# Schematic4.net
KiCad netlist of a schematic drawn in Altium Designer
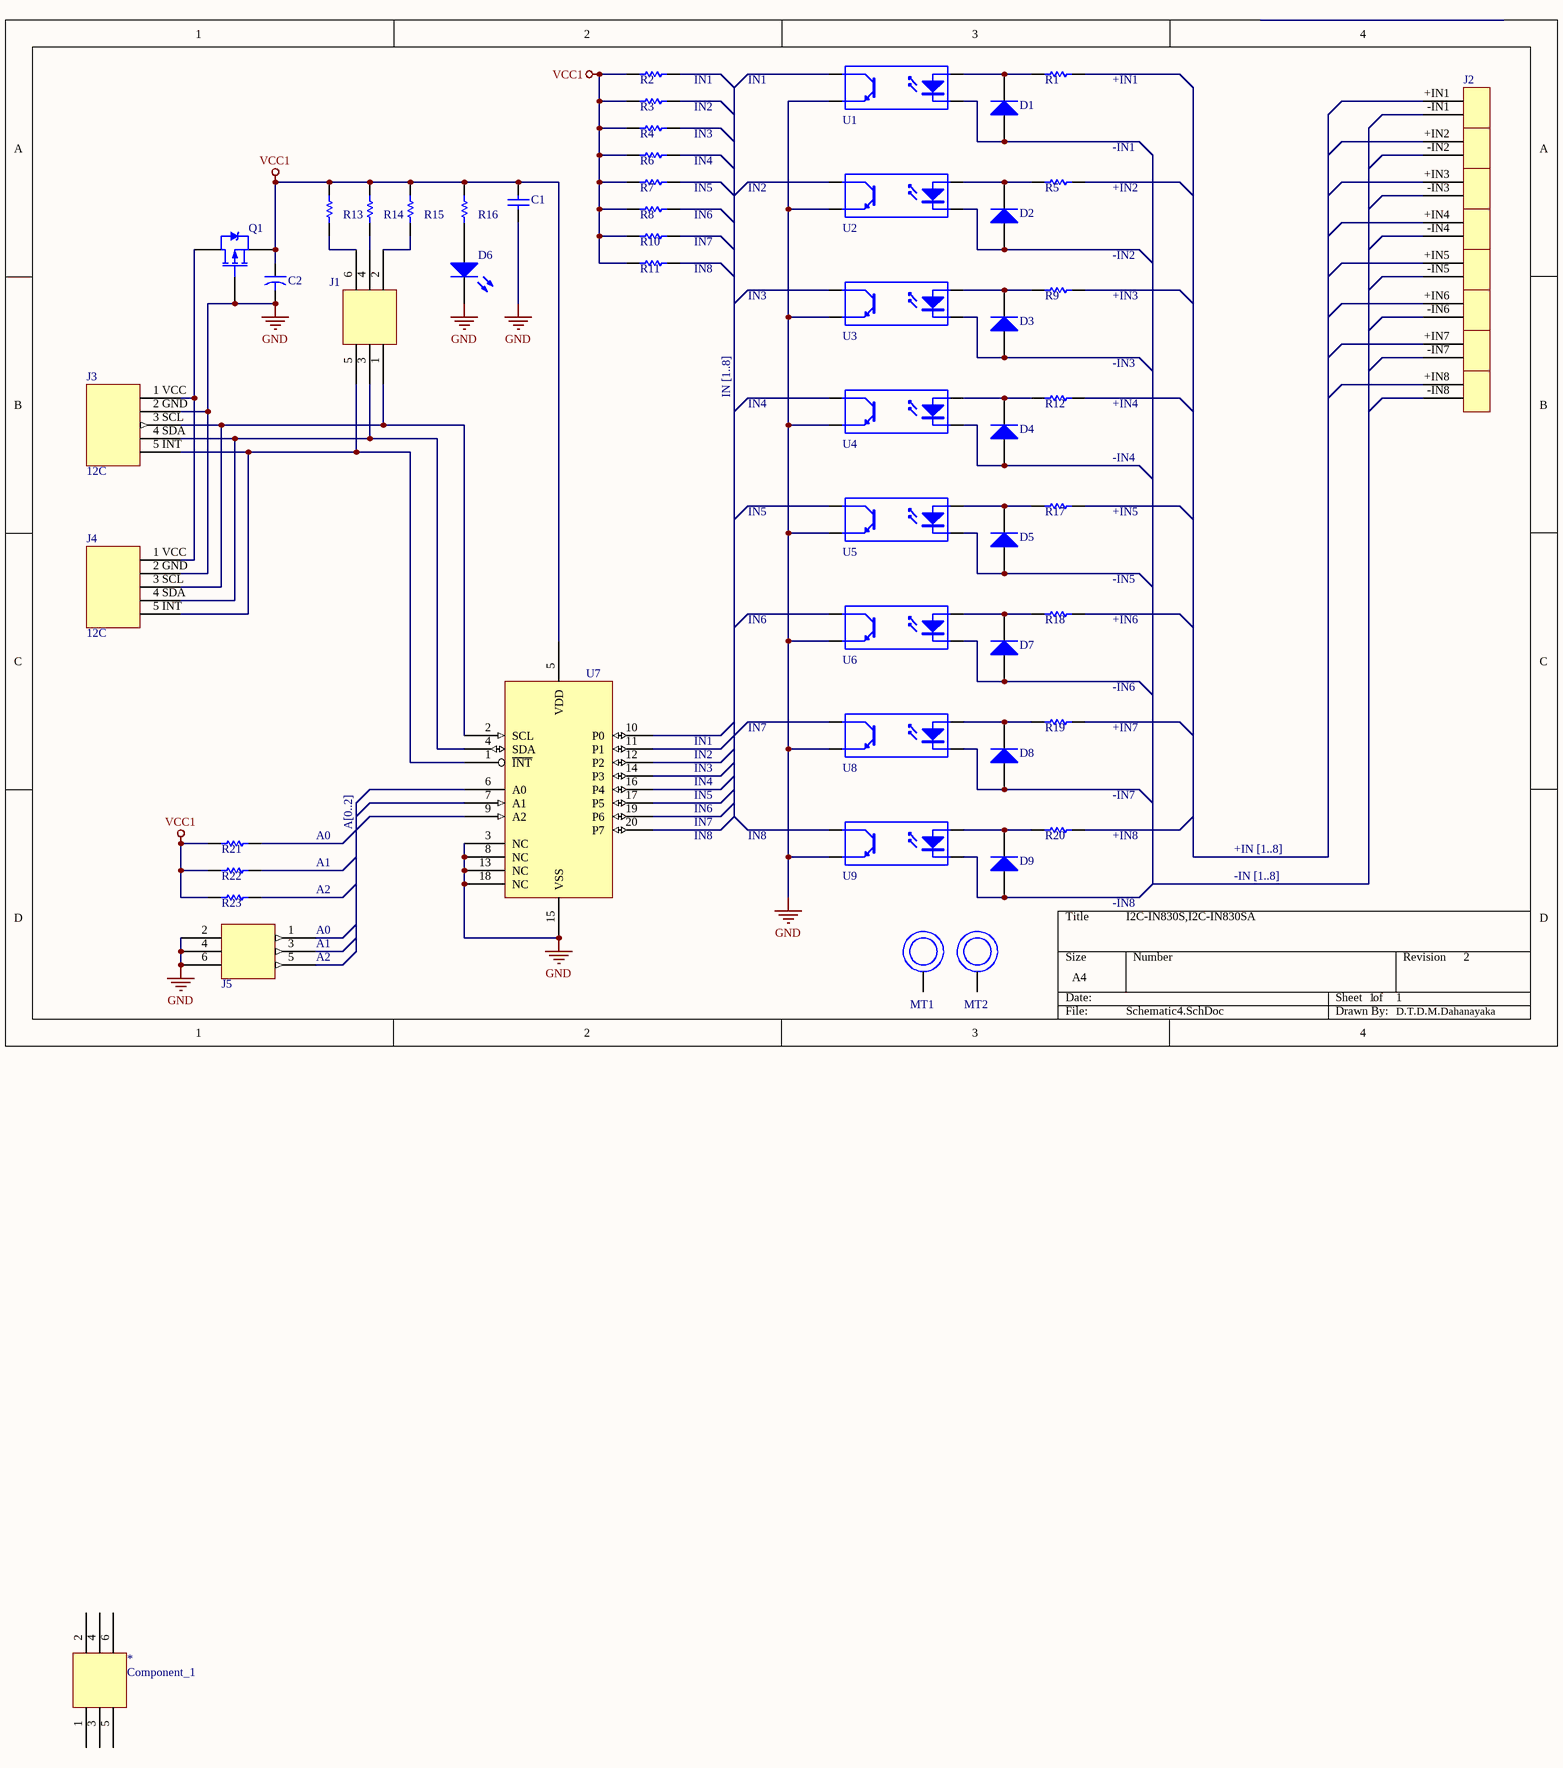
[diagram p0: Schematic4.SchDoc]

(export (version "E")
  (design (tool "Eeschema 10.0.6"))
  (components
    (comp (ref "*") (value "Component_1") (libsource (lib "J2") (part "Component_1")))
    (comp (ref "C1")
      (value "Cap")
      (footprint "RAD-0.3")
      (description "Capacitor")
      (fields (field (name "PUBLISHER") "Altium Limited"))
      (libsource (lib "Miscellaneous Devices") (part "Cap"))
    )
    (comp (ref "C2")
      (value "Cap2")
      (footprint "CAPR5-4X5")
      (description "Capacitor")
      (fields (field (name "PUBLISHER") "Altium Limited"))
      (libsource (lib "Miscellaneous Devices") (part "Cap2"))
    )
    (comp (ref "D1")
      (value "~")
      (footprint "SOT-23_N")
      (description "Silicon Low Leakage Diode")
      (fields (field (name "PUBLISHER") "Altium Limited"))
      (libsource (lib "Miscellaneous Devices") (part "Diode BAS116"))
    )
    (comp (ref "D2")
      (value "~")
      (footprint "SOT-23_N")
      (description "Silicon Low Leakage Diode")
      (fields (field (name "PUBLISHER") "Altium Limited"))
      (libsource (lib "Miscellaneous Devices") (part "Diode BAS116"))
    )
    (comp (ref "D3")
      (value "~")
      (footprint "SOT-23_N")
      (description "Silicon Low Leakage Diode")
      (fields (field (name "PUBLISHER") "Altium Limited"))
      (libsource (lib "Miscellaneous Devices") (part "Diode BAS116"))
    )
    (comp (ref "D4")
      (value "~")
      (footprint "SOT-23_N")
      (description "Silicon Low Leakage Diode")
      (fields (field (name "PUBLISHER") "Altium Limited"))
      (libsource (lib "Miscellaneous Devices") (part "Diode BAS116"))
    )
    (comp (ref "D5")
      (value "~")
      (footprint "SOT-23_N")
      (description "Silicon Low Leakage Diode")
      (fields (field (name "PUBLISHER") "Altium Limited"))
      (libsource (lib "Miscellaneous Devices") (part "Diode BAS116"))
    )
    (comp (ref "D6")
      (value "~")
      (footprint "LED-0")
      (description "Typical INFRARED GaAs LED")
      (fields (field (name "PUBLISHER") "Altium Limited"))
      (libsource (lib "Miscellaneous Devices") (part "LED0"))
    )
    (comp (ref "D7")
      (value "~")
      (footprint "SOT-23_N")
      (description "Silicon Low Leakage Diode")
      (fields (field (name "PUBLISHER") "Altium Limited"))
      (libsource (lib "Miscellaneous Devices") (part "Diode BAS116"))
    )
    (comp (ref "D8")
      (value "~")
      (footprint "SOT-23_N")
      (description "Silicon Low Leakage Diode")
      (fields (field (name "PUBLISHER") "Altium Limited"))
      (libsource (lib "Miscellaneous Devices") (part "Diode BAS116"))
    )
    (comp (ref "D9")
      (value "~")
      (footprint "SOT-23_N")
      (description "Silicon Low Leakage Diode")
      (fields (field (name "PUBLISHER") "Altium Limited"))
      (libsource (lib "Miscellaneous Devices") (part "Diode BAS116"))
    )
    (comp (ref "J1") (value "~") (libsource (lib "") (part "Component_1_1")))
    (comp (ref "J2") (value "~") (libsource (lib "J6") (part "Component_1")))
    (comp (ref "J3") (value "12C") (libsource (lib "J1") (part "Component_1")))
    (comp (ref "J4") (value "12C") (libsource (lib "J1") (part "Component_1")))
    (comp (ref "J5") (value "~") (libsource (lib "") (part "Component_1_2")))
    (comp (ref "MT1") (value "~") (libsource (lib "mt") (part "Component_1")))
    (comp (ref "MT2") (value "~") (libsource (lib "mt") (part "Component_1")))
    (comp (ref "Q1")
      (value "PMOS-2")
      (footprint "TO-220AB")
      (description "P-Channel Power MOSFET")
      (fields (field (name "PUBLISHER") "Altium Limited"))
      (libsource (lib "Miscellaneous Devices") (part "PMOS-2"))
    )
    (comp (ref "R1")
      (value "Res1")
      (footprint "AXIAL-0.3")
      (description "Resistor")
      (fields (field (name "PUBLISHER") "Altium Limited"))
      (libsource (lib "Miscellaneous Devices") (part "Res1"))
    )
    (comp (ref "R2")
      (value "Res1")
      (footprint "AXIAL-0.3")
      (description "Resistor")
      (fields (field (name "PUBLISHER") "Altium Limited"))
      (libsource (lib "Miscellaneous Devices") (part "Res1"))
    )
    (comp (ref "R3")
      (value "Res1")
      (footprint "AXIAL-0.3")
      (description "Resistor")
      (fields (field (name "PUBLISHER") "Altium Limited"))
      (libsource (lib "Miscellaneous Devices") (part "Res1"))
    )
    (comp (ref "R4")
      (value "Res1")
      (footprint "AXIAL-0.3")
      (description "Resistor")
      (fields (field (name "PUBLISHER") "Altium Limited"))
      (libsource (lib "Miscellaneous Devices") (part "Res1"))
    )
    (comp (ref "R5")
      (value "Res1")
      (footprint "AXIAL-0.3")
      (description "Resistor")
      (fields (field (name "PUBLISHER") "Altium Limited"))
      (libsource (lib "Miscellaneous Devices") (part "Res1"))
    )
    (comp (ref "R6")
      (value "Res1")
      (footprint "AXIAL-0.3")
      (description "Resistor")
      (fields (field (name "PUBLISHER") "Altium Limited"))
      (libsource (lib "Miscellaneous Devices") (part "Res1"))
    )
    (comp (ref "R7")
      (value "Res1")
      (footprint "AXIAL-0.3")
      (description "Resistor")
      (fields (field (name "PUBLISHER") "Altium Limited"))
      (libsource (lib "Miscellaneous Devices") (part "Res1"))
    )
    (comp (ref "R8")
      (value "Res1")
      (footprint "AXIAL-0.3")
      (description "Resistor")
      (fields (field (name "PUBLISHER") "Altium Limited"))
      (libsource (lib "Miscellaneous Devices") (part "Res1"))
    )
    (comp (ref "R9")
      (value "Res1")
      (footprint "AXIAL-0.3")
      (description "Resistor")
      (fields (field (name "PUBLISHER") "Altium Limited"))
      (libsource (lib "Miscellaneous Devices") (part "Res1"))
    )
    (comp (ref "R10")
      (value "Res1")
      (footprint "AXIAL-0.3")
      (description "Resistor")
      (fields (field (name "PUBLISHER") "Altium Limited"))
      (libsource (lib "Miscellaneous Devices") (part "Res1"))
    )
    (comp (ref "R11")
      (value "Res1")
      (footprint "AXIAL-0.3")
      (description "Resistor")
      (fields (field (name "PUBLISHER") "Altium Limited"))
      (libsource (lib "Miscellaneous Devices") (part "Res1"))
    )
    (comp (ref "R12")
      (value "Res1")
      (footprint "AXIAL-0.3")
      (description "Resistor")
      (fields (field (name "PUBLISHER") "Altium Limited"))
      (libsource (lib "Miscellaneous Devices") (part "Res1"))
    )
    (comp (ref "R13")
      (value "Res1")
      (footprint "AXIAL-0.3")
      (description "Resistor")
      (fields (field (name "PUBLISHER") "Altium Limited"))
      (libsource (lib "Miscellaneous Devices") (part "Res1"))
    )
    (comp (ref "R14")
      (value "Res1")
      (footprint "AXIAL-0.3")
      (description "Resistor")
      (fields (field (name "PUBLISHER") "Altium Limited"))
      (libsource (lib "Miscellaneous Devices") (part "Res1"))
    )
    (comp (ref "R15")
      (value "Res1")
      (footprint "AXIAL-0.3")
      (description "Resistor")
      (fields (field (name "PUBLISHER") "Altium Limited"))
      (libsource (lib "Miscellaneous Devices") (part "Res1"))
    )
    (comp (ref "R16")
      (value "Res1")
      (footprint "AXIAL-0.3")
      (description "Resistor")
      (fields (field (name "PUBLISHER") "Altium Limited"))
      (libsource (lib "Miscellaneous Devices") (part "Res1"))
    )
    (comp (ref "R17")
      (value "Res1")
      (footprint "AXIAL-0.3")
      (description "Resistor")
      (fields (field (name "PUBLISHER") "Altium Limited"))
      (libsource (lib "Miscellaneous Devices") (part "Res1"))
    )
    (comp (ref "R18")
      (value "Res1")
      (footprint "AXIAL-0.3")
      (description "Resistor")
      (fields (field (name "PUBLISHER") "Altium Limited"))
      (libsource (lib "Miscellaneous Devices") (part "Res1"))
    )
    (comp (ref "R19")
      (value "Res1")
      (footprint "AXIAL-0.3")
      (description "Resistor")
      (fields (field (name "PUBLISHER") "Altium Limited"))
      (libsource (lib "Miscellaneous Devices") (part "Res1"))
    )
    (comp (ref "R20")
      (value "Res1")
      (footprint "AXIAL-0.3")
      (description "Resistor")
      (fields (field (name "PUBLISHER") "Altium Limited"))
      (libsource (lib "Miscellaneous Devices") (part "Res1"))
    )
    (comp (ref "R21")
      (value "Res1")
      (footprint "AXIAL-0.3")
      (description "Resistor")
      (fields (field (name "PUBLISHER") "Altium Limited"))
      (libsource (lib "Miscellaneous Devices") (part "Res1"))
    )
    (comp (ref "R22")
      (value "Res1")
      (footprint "AXIAL-0.3")
      (description "Resistor")
      (fields (field (name "PUBLISHER") "Altium Limited"))
      (libsource (lib "Miscellaneous Devices") (part "Res1"))
    )
    (comp (ref "R23")
      (value "Res1")
      (footprint "AXIAL-0.3")
      (description "Resistor")
      (fields (field (name "PUBLISHER") "Altium Limited"))
      (libsource (lib "Miscellaneous Devices") (part "Res1"))
    )
    (comp (ref "U1")
      (value "~")
      (footprint "DIP-4")
      (description "4-Pin Phototransistor Optocoupler")
      (fields (field (name "PUBLISHER") "Altium Limited"))
      (libsource (lib "Miscellaneous Devices") (part "Optoisolator1"))
    )
    (comp (ref "U2")
      (value "~")
      (footprint "DIP-4")
      (description "4-Pin Phototransistor Optocoupler")
      (fields (field (name "PUBLISHER") "Altium Limited"))
      (libsource (lib "Miscellaneous Devices") (part "Optoisolator1"))
    )
    (comp (ref "U3")
      (value "~")
      (footprint "DIP-4")
      (description "4-Pin Phototransistor Optocoupler")
      (fields (field (name "PUBLISHER") "Altium Limited"))
      (libsource (lib "Miscellaneous Devices") (part "Optoisolator1"))
    )
    (comp (ref "U4")
      (value "~")
      (footprint "DIP-4")
      (description "4-Pin Phototransistor Optocoupler")
      (fields (field (name "PUBLISHER") "Altium Limited"))
      (libsource (lib "Miscellaneous Devices") (part "Optoisolator1"))
    )
    (comp (ref "U5")
      (value "~")
      (footprint "DIP-4")
      (description "4-Pin Phototransistor Optocoupler")
      (fields (field (name "PUBLISHER") "Altium Limited"))
      (libsource (lib "Miscellaneous Devices") (part "Optoisolator1"))
    )
    (comp (ref "U6")
      (value "~")
      (footprint "DIP-4")
      (description "4-Pin Phototransistor Optocoupler")
      (fields (field (name "PUBLISHER") "Altium Limited"))
      (libsource (lib "Miscellaneous Devices") (part "Optoisolator1"))
    )
    (comp (ref "U7") (value "~") (libsource (lib "U1") (part "Component_1")))
    (comp (ref "U8")
      (value "~")
      (footprint "DIP-4")
      (description "4-Pin Phototransistor Optocoupler")
      (fields (field (name "PUBLISHER") "Altium Limited"))
      (libsource (lib "Miscellaneous Devices") (part "Optoisolator1"))
    )
    (comp (ref "U9")
      (value "~")
      (footprint "DIP-4")
      (description "4-Pin Phototransistor Optocoupler")
      (fields (field (name "PUBLISHER") "Altium Limited"))
      (libsource (lib "Miscellaneous Devices") (part "Optoisolator1"))
    )
  )
  (nets
    (net (code "1") (name "GND") (class "Default")
      (node (ref "C1") (pin "1") (pinfunction "1_1") (pintype "passive"))
      (node (ref "C2") (pin "2") (pinfunction "2_2") (pintype "passive"))
      (node (ref "D6") (pin "2") (pinfunction "K_2") (pintype "passive"))
      (node (ref "J3") (pin "2_GND") (pintype "passive"))
      (node (ref "J4") (pin "2_GND") (pintype "passive"))
      (node (ref "J5") (pin "2") (pintype "passive"))
      (node (ref "J5") (pin "4") (pintype "passive"))
      (node (ref "J5") (pin "6") (pintype "passive"))
      (node (ref "Q1") (pin "1") (pinfunction "G_1") (pintype "passive"))
      (node (ref "U1") (pin "3") (pinfunction "E_3") (pintype "passive"))
      (node (ref "U2") (pin "3") (pinfunction "E_3") (pintype "passive"))
      (node (ref "U3") (pin "3") (pinfunction "E_3") (pintype "passive"))
      (node (ref "U4") (pin "3") (pinfunction "E_3") (pintype "passive"))
      (node (ref "U5") (pin "3") (pinfunction "E_3") (pintype "passive"))
      (node (ref "U6") (pin "3") (pinfunction "E_3") (pintype "passive"))
      (node (ref "U7") (pin "13") (pinfunction "NC_13") (pintype "passive"))
      (node (ref "U7") (pin "15") (pinfunction "VSS_15") (pintype "passive"))
      (node (ref "U7") (pin "18") (pinfunction "NC_18") (pintype "passive"))
      (node (ref "U7") (pin "3") (pinfunction "NC_3") (pintype "passive"))
      (node (ref "U7") (pin "8") (pinfunction "NC_8") (pintype "passive"))
      (node (ref "U8") (pin "3") (pinfunction "E_3") (pintype "passive"))
      (node (ref "U9") (pin "3") (pinfunction "E_3") (pintype "passive"))
    )
    (net (code "2") (name "Net-(D1-A)") (class "Default")
      (node (ref "D1") (pin "1") (pinfunction "A_1") (pintype "passive"))
      (node (ref "U1") (pin "2") (pinfunction "K_2") (pintype "passive"))
    )
    (net (code "3") (name "Net-(D1-K)") (class "Default")
      (node (ref "D1") (pin "3") (pinfunction "K_3") (pintype "passive"))
      (node (ref "R1") (pin "1") (pinfunction "1_1") (pintype "passive"))
      (node (ref "U1") (pin "1") (pinfunction "A_1") (pintype "passive"))
    )
    (net (code "4") (name "Net-(D2-A)") (class "Default")
      (node (ref "D2") (pin "1") (pinfunction "A_1") (pintype "passive"))
      (node (ref "U2") (pin "2") (pinfunction "K_2") (pintype "passive"))
    )
    (net (code "5") (name "Net-(D2-K)") (class "Default")
      (node (ref "D2") (pin "3") (pinfunction "K_3") (pintype "passive"))
      (node (ref "R5") (pin "1") (pinfunction "1_1") (pintype "passive"))
      (node (ref "U2") (pin "1") (pinfunction "A_1") (pintype "passive"))
    )
    (net (code "6") (name "Net-(D3-A)") (class "Default")
      (node (ref "D3") (pin "1") (pinfunction "A_1") (pintype "passive"))
      (node (ref "U3") (pin "2") (pinfunction "K_2") (pintype "passive"))
    )
    (net (code "7") (name "Net-(D3-K)") (class "Default")
      (node (ref "D3") (pin "3") (pinfunction "K_3") (pintype "passive"))
      (node (ref "R9") (pin "1") (pinfunction "1_1") (pintype "passive"))
      (node (ref "U3") (pin "1") (pinfunction "A_1") (pintype "passive"))
    )
    (net (code "8") (name "Net-(D4-A)") (class "Default")
      (node (ref "D4") (pin "1") (pinfunction "A_1") (pintype "passive"))
      (node (ref "U4") (pin "2") (pinfunction "K_2") (pintype "passive"))
    )
    (net (code "9") (name "Net-(D4-K)") (class "Default")
      (node (ref "D4") (pin "3") (pinfunction "K_3") (pintype "passive"))
      (node (ref "R12") (pin "1") (pinfunction "1_1") (pintype "passive"))
      (node (ref "U4") (pin "1") (pinfunction "A_1") (pintype "passive"))
    )
    (net (code "10") (name "Net-(D5-A)") (class "Default")
      (node (ref "D5") (pin "1") (pinfunction "A_1") (pintype "passive"))
      (node (ref "U5") (pin "2") (pinfunction "K_2") (pintype "passive"))
    )
    (net (code "11") (name "Net-(D5-K)") (class "Default")
      (node (ref "D5") (pin "3") (pinfunction "K_3") (pintype "passive"))
      (node (ref "R17") (pin "1") (pinfunction "1_1") (pintype "passive"))
      (node (ref "U5") (pin "1") (pinfunction "A_1") (pintype "passive"))
    )
    (net (code "12") (name "Net-(D6-A)") (class "Default")
      (node (ref "D6") (pin "1") (pinfunction "A_1") (pintype "passive"))
      (node (ref "R16") (pin "1") (pinfunction "1_1") (pintype "passive"))
    )
    (net (code "13") (name "Net-(D7-A)") (class "Default")
      (node (ref "D7") (pin "1") (pinfunction "A_1") (pintype "passive"))
      (node (ref "U6") (pin "2") (pinfunction "K_2") (pintype "passive"))
    )
    (net (code "14") (name "Net-(D7-K)") (class "Default")
      (node (ref "D7") (pin "3") (pinfunction "K_3") (pintype "passive"))
      (node (ref "R18") (pin "1") (pinfunction "1_1") (pintype "passive"))
      (node (ref "U6") (pin "1") (pinfunction "A_1") (pintype "passive"))
    )
    (net (code "15") (name "Net-(D8-A)") (class "Default")
      (node (ref "D8") (pin "1") (pinfunction "A_1") (pintype "passive"))
      (node (ref "U8") (pin "2") (pinfunction "K_2") (pintype "passive"))
    )
    (net (code "16") (name "Net-(D8-K)") (class "Default")
      (node (ref "D8") (pin "3") (pinfunction "K_3") (pintype "passive"))
      (node (ref "R19") (pin "1") (pinfunction "1_1") (pintype "passive"))
      (node (ref "U8") (pin "1") (pinfunction "A_1") (pintype "passive"))
    )
    (net (code "17") (name "Net-(D9-A)") (class "Default")
      (node (ref "D9") (pin "1") (pinfunction "A_1") (pintype "passive"))
      (node (ref "U9") (pin "2") (pinfunction "K_2") (pintype "passive"))
    )
    (net (code "18") (name "Net-(D9-K)") (class "Default")
      (node (ref "D9") (pin "3") (pinfunction "K_3") (pintype "passive"))
      (node (ref "R20") (pin "1") (pinfunction "1_1") (pintype "passive"))
      (node (ref "U9") (pin "1") (pinfunction "A_1") (pintype "passive"))
    )
    (net (code "19") (name "Net-(J1-Pad2)") (class "Default")
      (node (ref "J1") (pin "2") (pintype "passive"))
      (node (ref "R15") (pin "1") (pinfunction "1_1") (pintype "passive"))
    )
    (net (code "20") (name "Net-(J1-Pad4)") (class "Default")
      (node (ref "J1") (pin "4") (pintype "passive"))
      (node (ref "R14") (pin "1") (pinfunction "1_1") (pintype "passive"))
    )
    (net (code "21") (name "Net-(J1-Pad6)") (class "Default")
      (node (ref "J1") (pin "6") (pintype "passive"))
      (node (ref "R13") (pin "1") (pinfunction "1_1") (pintype "passive"))
    )
    (net (code "22") (name "Net-(Q1-D)") (class "Default")
      (node (ref "J3") (pin "1_VCC") (pintype "passive"))
      (node (ref "J4") (pin "1_VCC") (pintype "passive"))
      (node (ref "Q1") (pin "2") (pinfunction "D_2") (pintype "passive"))
    )
    (net (code "23") (name "Net-(U7-SCL)") (class "Default")
      (node (ref "J1") (pin "1") (pintype "passive"))
      (node (ref "J3") (pin "3_SCL") (pintype "passive"))
      (node (ref "J4") (pin "3_SCL") (pintype "passive"))
      (node (ref "U7") (pin "2") (pinfunction "SCL_2") (pintype "input"))
    )
    (net (code "24") (name "Net-(U7-SDA)") (class "Default")
      (node (ref "J1") (pin "3") (pintype "passive"))
      (node (ref "J3") (pin "4_SDA") (pintype "passive"))
      (node (ref "J4") (pin "4_SDA") (pintype "passive"))
      (node (ref "U7") (pin "4") (pinfunction "SDA_4") (pintype "bidirectional"))
    )
    (net (code "25") (name "Net-(U7-~{INT})") (class "Default")
      (node (ref "J1") (pin "5") (pintype "passive"))
      (node (ref "J3") (pin "5_INT") (pintype "passive"))
      (node (ref "J4") (pin "5_INT") (pintype "passive"))
      (node (ref "U7") (pin "1") (pinfunction "~{INT}_1") (pintype "passive"))
    )
    (net (code "26") (name "VCC1") (class "Default")
      (node (ref "C1") (pin "2") (pinfunction "2_2") (pintype "passive"))
      (node (ref "C2") (pin "1") (pinfunction "1_1") (pintype "passive"))
      (node (ref "Q1") (pin "3") (pinfunction "S_3") (pintype "passive"))
      (node (ref "R10") (pin "1") (pinfunction "1_1") (pintype "passive"))
      (node (ref "R11") (pin "1") (pinfunction "1_1") (pintype "passive"))
      (node (ref "R13") (pin "2") (pinfunction "2_2") (pintype "passive"))
      (node (ref "R14") (pin "2") (pinfunction "2_2") (pintype "passive"))
      (node (ref "R15") (pin "2") (pinfunction "2_2") (pintype "passive"))
      (node (ref "R16") (pin "2") (pinfunction "2_2") (pintype "passive"))
      (node (ref "R2") (pin "1") (pinfunction "1_1") (pintype "passive"))
      (node (ref "R21") (pin "2") (pinfunction "2_2") (pintype "passive"))
      (node (ref "R22") (pin "2") (pinfunction "2_2") (pintype "passive"))
      (node (ref "R23") (pin "2") (pinfunction "2_2") (pintype "passive"))
      (node (ref "R3") (pin "1") (pinfunction "1_1") (pintype "passive"))
      (node (ref "R4") (pin "1") (pinfunction "1_1") (pintype "passive"))
      (node (ref "R6") (pin "1") (pinfunction "1_1") (pintype "passive"))
      (node (ref "R7") (pin "1") (pinfunction "1_1") (pintype "passive"))
      (node (ref "R8") (pin "1") (pinfunction "1_1") (pintype "passive"))
      (node (ref "U7") (pin "5") (pinfunction "VDD_5") (pintype "passive"))
    )
    (net (code "27") (name "unconnected-(*-Pad1)") (class "Default")
      (node (ref "*") (pin "1") (pintype "passive"))
    )
    (net (code "28") (name "unconnected-(*-Pad2)") (class "Default")
      (node (ref "*") (pin "2") (pintype "passive"))
    )
    (net (code "29") (name "unconnected-(*-Pad3)") (class "Default")
      (node (ref "*") (pin "3") (pintype "passive"))
    )
    (net (code "30") (name "unconnected-(*-Pad4)") (class "Default")
      (node (ref "*") (pin "4") (pintype "passive"))
    )
    (net (code "31") (name "unconnected-(*-Pad5)") (class "Default")
      (node (ref "*") (pin "5") (pintype "passive"))
    )
    (net (code "32") (name "unconnected-(*-Pad6)") (class "Default")
      (node (ref "*") (pin "6") (pintype "passive"))
    )
    (net (code "33") (name "unconnected-(J2-Pad+IN1)") (class "Default")
      (node (ref "J2") (pin "+IN1") (pintype "passive"))
    )
    (net (code "34") (name "unconnected-(J2-Pad+IN2)") (class "Default")
      (node (ref "J2") (pin "+IN2") (pintype "passive"))
    )
    (net (code "35") (name "unconnected-(J2-Pad+IN3)") (class "Default")
      (node (ref "J2") (pin "+IN3") (pintype "passive"))
    )
    (net (code "36") (name "unconnected-(J2-Pad+IN4)") (class "Default")
      (node (ref "J2") (pin "+IN4") (pintype "passive"))
    )
    (net (code "37") (name "unconnected-(J2-Pad+IN5)") (class "Default")
      (node (ref "J2") (pin "+IN5") (pintype "passive"))
    )
    (net (code "38") (name "unconnected-(J2-Pad+IN6)") (class "Default")
      (node (ref "J2") (pin "+IN6") (pintype "passive"))
    )
    (net (code "39") (name "unconnected-(J2-Pad+IN7)") (class "Default")
      (node (ref "J2") (pin "+IN7") (pintype "passive"))
    )
    (net (code "40") (name "unconnected-(J2-Pad+IN8)") (class "Default")
      (node (ref "J2") (pin "+IN8") (pintype "passive"))
    )
    (net (code "41") (name "unconnected-(J2-Pad-IN1)") (class "Default")
      (node (ref "J2") (pin "-IN1") (pintype "passive"))
    )
    (net (code "42") (name "unconnected-(J2-Pad-IN2)") (class "Default")
      (node (ref "J2") (pin "-IN2") (pintype "passive"))
    )
    (net (code "43") (name "unconnected-(J2-Pad-IN3)") (class "Default")
      (node (ref "J2") (pin "-IN3") (pintype "passive"))
    )
    (net (code "44") (name "unconnected-(J2-Pad-IN4)") (class "Default")
      (node (ref "J2") (pin "-IN4") (pintype "passive"))
    )
    (net (code "45") (name "unconnected-(J2-Pad-IN5)") (class "Default")
      (node (ref "J2") (pin "-IN5") (pintype "passive"))
    )
    (net (code "46") (name "unconnected-(J2-Pad-IN6)") (class "Default")
      (node (ref "J2") (pin "-IN6") (pintype "passive"))
    )
    (net (code "47") (name "unconnected-(J2-Pad-IN7)") (class "Default")
      (node (ref "J2") (pin "-IN7") (pintype "passive"))
    )
    (net (code "48") (name "unconnected-(J2-Pad-IN8)") (class "Default")
      (node (ref "J2") (pin "-IN8") (pintype "passive"))
    )
    (net (code "49") (name "unconnected-(J5-Pad1)") (class "Default")
      (node (ref "J5") (pin "1") (pintype "output"))
    )
    (net (code "50") (name "unconnected-(J5-Pad3)") (class "Default")
      (node (ref "J5") (pin "3") (pintype "output"))
    )
    (net (code "51") (name "unconnected-(J5-Pad5)") (class "Default")
      (node (ref "J5") (pin "5") (pintype "output"))
    )
    (net (code "52") (name "unconnected-(MT1-Pad)") (class "Default")
      (node (ref "MT1") (pin "") (pintype "power_in"))
    )
    (net (code "53") (name "unconnected-(MT2-Pad)") (class "Default")
      (node (ref "MT2") (pin "") (pintype "power_in"))
    )
    (net (code "54") (name "unconnected-(R1-Pad2)") (class "Default")
      (node (ref "R1") (pin "2") (pinfunction "2_2") (pintype "passive"))
    )
    (net (code "55") (name "unconnected-(R2-Pad2)") (class "Default")
      (node (ref "R2") (pin "2") (pinfunction "2_2") (pintype "passive"))
    )
    (net (code "56") (name "unconnected-(R3-Pad2)") (class "Default")
      (node (ref "R3") (pin "2") (pinfunction "2_2") (pintype "passive"))
    )
    (net (code "57") (name "unconnected-(R4-Pad2)") (class "Default")
      (node (ref "R4") (pin "2") (pinfunction "2_2") (pintype "passive"))
    )
    (net (code "58") (name "unconnected-(R5-Pad2)") (class "Default")
      (node (ref "R5") (pin "2") (pinfunction "2_2") (pintype "passive"))
    )
    (net (code "59") (name "unconnected-(R6-Pad2)") (class "Default")
      (node (ref "R6") (pin "2") (pinfunction "2_2") (pintype "passive"))
    )
    (net (code "60") (name "unconnected-(R7-Pad2)") (class "Default")
      (node (ref "R7") (pin "2") (pinfunction "2_2") (pintype "passive"))
    )
    (net (code "61") (name "unconnected-(R8-Pad2)") (class "Default")
      (node (ref "R8") (pin "2") (pinfunction "2_2") (pintype "passive"))
    )
    (net (code "62") (name "unconnected-(R9-Pad2)") (class "Default")
      (node (ref "R9") (pin "2") (pinfunction "2_2") (pintype "passive"))
    )
    (net (code "63") (name "unconnected-(R10-Pad2)") (class "Default")
      (node (ref "R10") (pin "2") (pinfunction "2_2") (pintype "passive"))
    )
    (net (code "64") (name "unconnected-(R11-Pad2)") (class "Default")
      (node (ref "R11") (pin "2") (pinfunction "2_2") (pintype "passive"))
    )
    (net (code "65") (name "unconnected-(R12-Pad2)") (class "Default")
      (node (ref "R12") (pin "2") (pinfunction "2_2") (pintype "passive"))
    )
    (net (code "66") (name "unconnected-(R17-Pad2)") (class "Default")
      (node (ref "R17") (pin "2") (pinfunction "2_2") (pintype "passive"))
    )
    (net (code "67") (name "unconnected-(R18-Pad2)") (class "Default")
      (node (ref "R18") (pin "2") (pinfunction "2_2") (pintype "passive"))
    )
    (net (code "68") (name "unconnected-(R19-Pad2)") (class "Default")
      (node (ref "R19") (pin "2") (pinfunction "2_2") (pintype "passive"))
    )
    (net (code "69") (name "unconnected-(R20-Pad2)") (class "Default")
      (node (ref "R20") (pin "2") (pinfunction "2_2") (pintype "passive"))
    )
    (net (code "70") (name "unconnected-(R21-Pad1)") (class "Default")
      (node (ref "R21") (pin "1") (pinfunction "1_1") (pintype "passive"))
    )
    (net (code "71") (name "unconnected-(R22-Pad1)") (class "Default")
      (node (ref "R22") (pin "1") (pinfunction "1_1") (pintype "passive"))
    )
    (net (code "72") (name "unconnected-(R23-Pad1)") (class "Default")
      (node (ref "R23") (pin "1") (pinfunction "1_1") (pintype "passive"))
    )
    (net (code "73") (name "unconnected-(U1-C-Pad4)") (class "Default")
      (node (ref "U1") (pin "4") (pinfunction "C_4") (pintype "passive"))
    )
    (net (code "74") (name "unconnected-(U2-C-Pad4)") (class "Default")
      (node (ref "U2") (pin "4") (pinfunction "C_4") (pintype "passive"))
    )
    (net (code "75") (name "unconnected-(U3-C-Pad4)") (class "Default")
      (node (ref "U3") (pin "4") (pinfunction "C_4") (pintype "passive"))
    )
    (net (code "76") (name "unconnected-(U4-C-Pad4)") (class "Default")
      (node (ref "U4") (pin "4") (pinfunction "C_4") (pintype "passive"))
    )
    (net (code "77") (name "unconnected-(U5-C-Pad4)") (class "Default")
      (node (ref "U5") (pin "4") (pinfunction "C_4") (pintype "passive"))
    )
    (net (code "78") (name "unconnected-(U6-C-Pad4)") (class "Default")
      (node (ref "U6") (pin "4") (pinfunction "C_4") (pintype "passive"))
    )
    (net (code "79") (name "unconnected-(U7-A0-Pad6)") (class "Default")
      (node (ref "U7") (pin "6") (pinfunction "A0_6") (pintype "passive"))
    )
    (net (code "80") (name "unconnected-(U7-A1-Pad7)") (class "Default")
      (node (ref "U7") (pin "7") (pinfunction "A1_7") (pintype "input"))
    )
    (net (code "81") (name "unconnected-(U7-A2-Pad9)") (class "Default")
      (node (ref "U7") (pin "9") (pinfunction "A2_9") (pintype "input"))
    )
    (net (code "82") (name "unconnected-(U7-P0-Pad10)") (class "Default")
      (node (ref "U7") (pin "10") (pinfunction "P0_10") (pintype "bidirectional"))
    )
    (net (code "83") (name "unconnected-(U7-P1-Pad11)") (class "Default")
      (node (ref "U7") (pin "11") (pinfunction "P1_11") (pintype "bidirectional"))
    )
    (net (code "84") (name "unconnected-(U7-P2-Pad12)") (class "Default")
      (node (ref "U7") (pin "12") (pinfunction "P2_12") (pintype "bidirectional"))
    )
    (net (code "85") (name "unconnected-(U7-P3-Pad14)") (class "Default")
      (node (ref "U7") (pin "14") (pinfunction "P3_14") (pintype "bidirectional"))
    )
    (net (code "86") (name "unconnected-(U7-P4-Pad16)") (class "Default")
      (node (ref "U7") (pin "16") (pinfunction "P4_16") (pintype "bidirectional"))
    )
    (net (code "87") (name "unconnected-(U7-P5-Pad17)") (class "Default")
      (node (ref "U7") (pin "17") (pinfunction "P5_17") (pintype "bidirectional"))
    )
    (net (code "88") (name "unconnected-(U7-P6-Pad19)") (class "Default")
      (node (ref "U7") (pin "19") (pinfunction "P6_19") (pintype "bidirectional"))
    )
    (net (code "89") (name "unconnected-(U7-P7-Pad20)") (class "Default")
      (node (ref "U7") (pin "20") (pinfunction "P7_20") (pintype "bidirectional"))
    )
    (net (code "90") (name "unconnected-(U8-C-Pad4)") (class "Default")
      (node (ref "U8") (pin "4") (pinfunction "C_4") (pintype "passive"))
    )
    (net (code "91") (name "unconnected-(U9-C-Pad4)") (class "Default")
      (node (ref "U9") (pin "4") (pinfunction "C_4") (pintype "passive"))
    )
  )
)
